# FPGA.net
KiCad netlist of a schematic drawn in Altium Designer
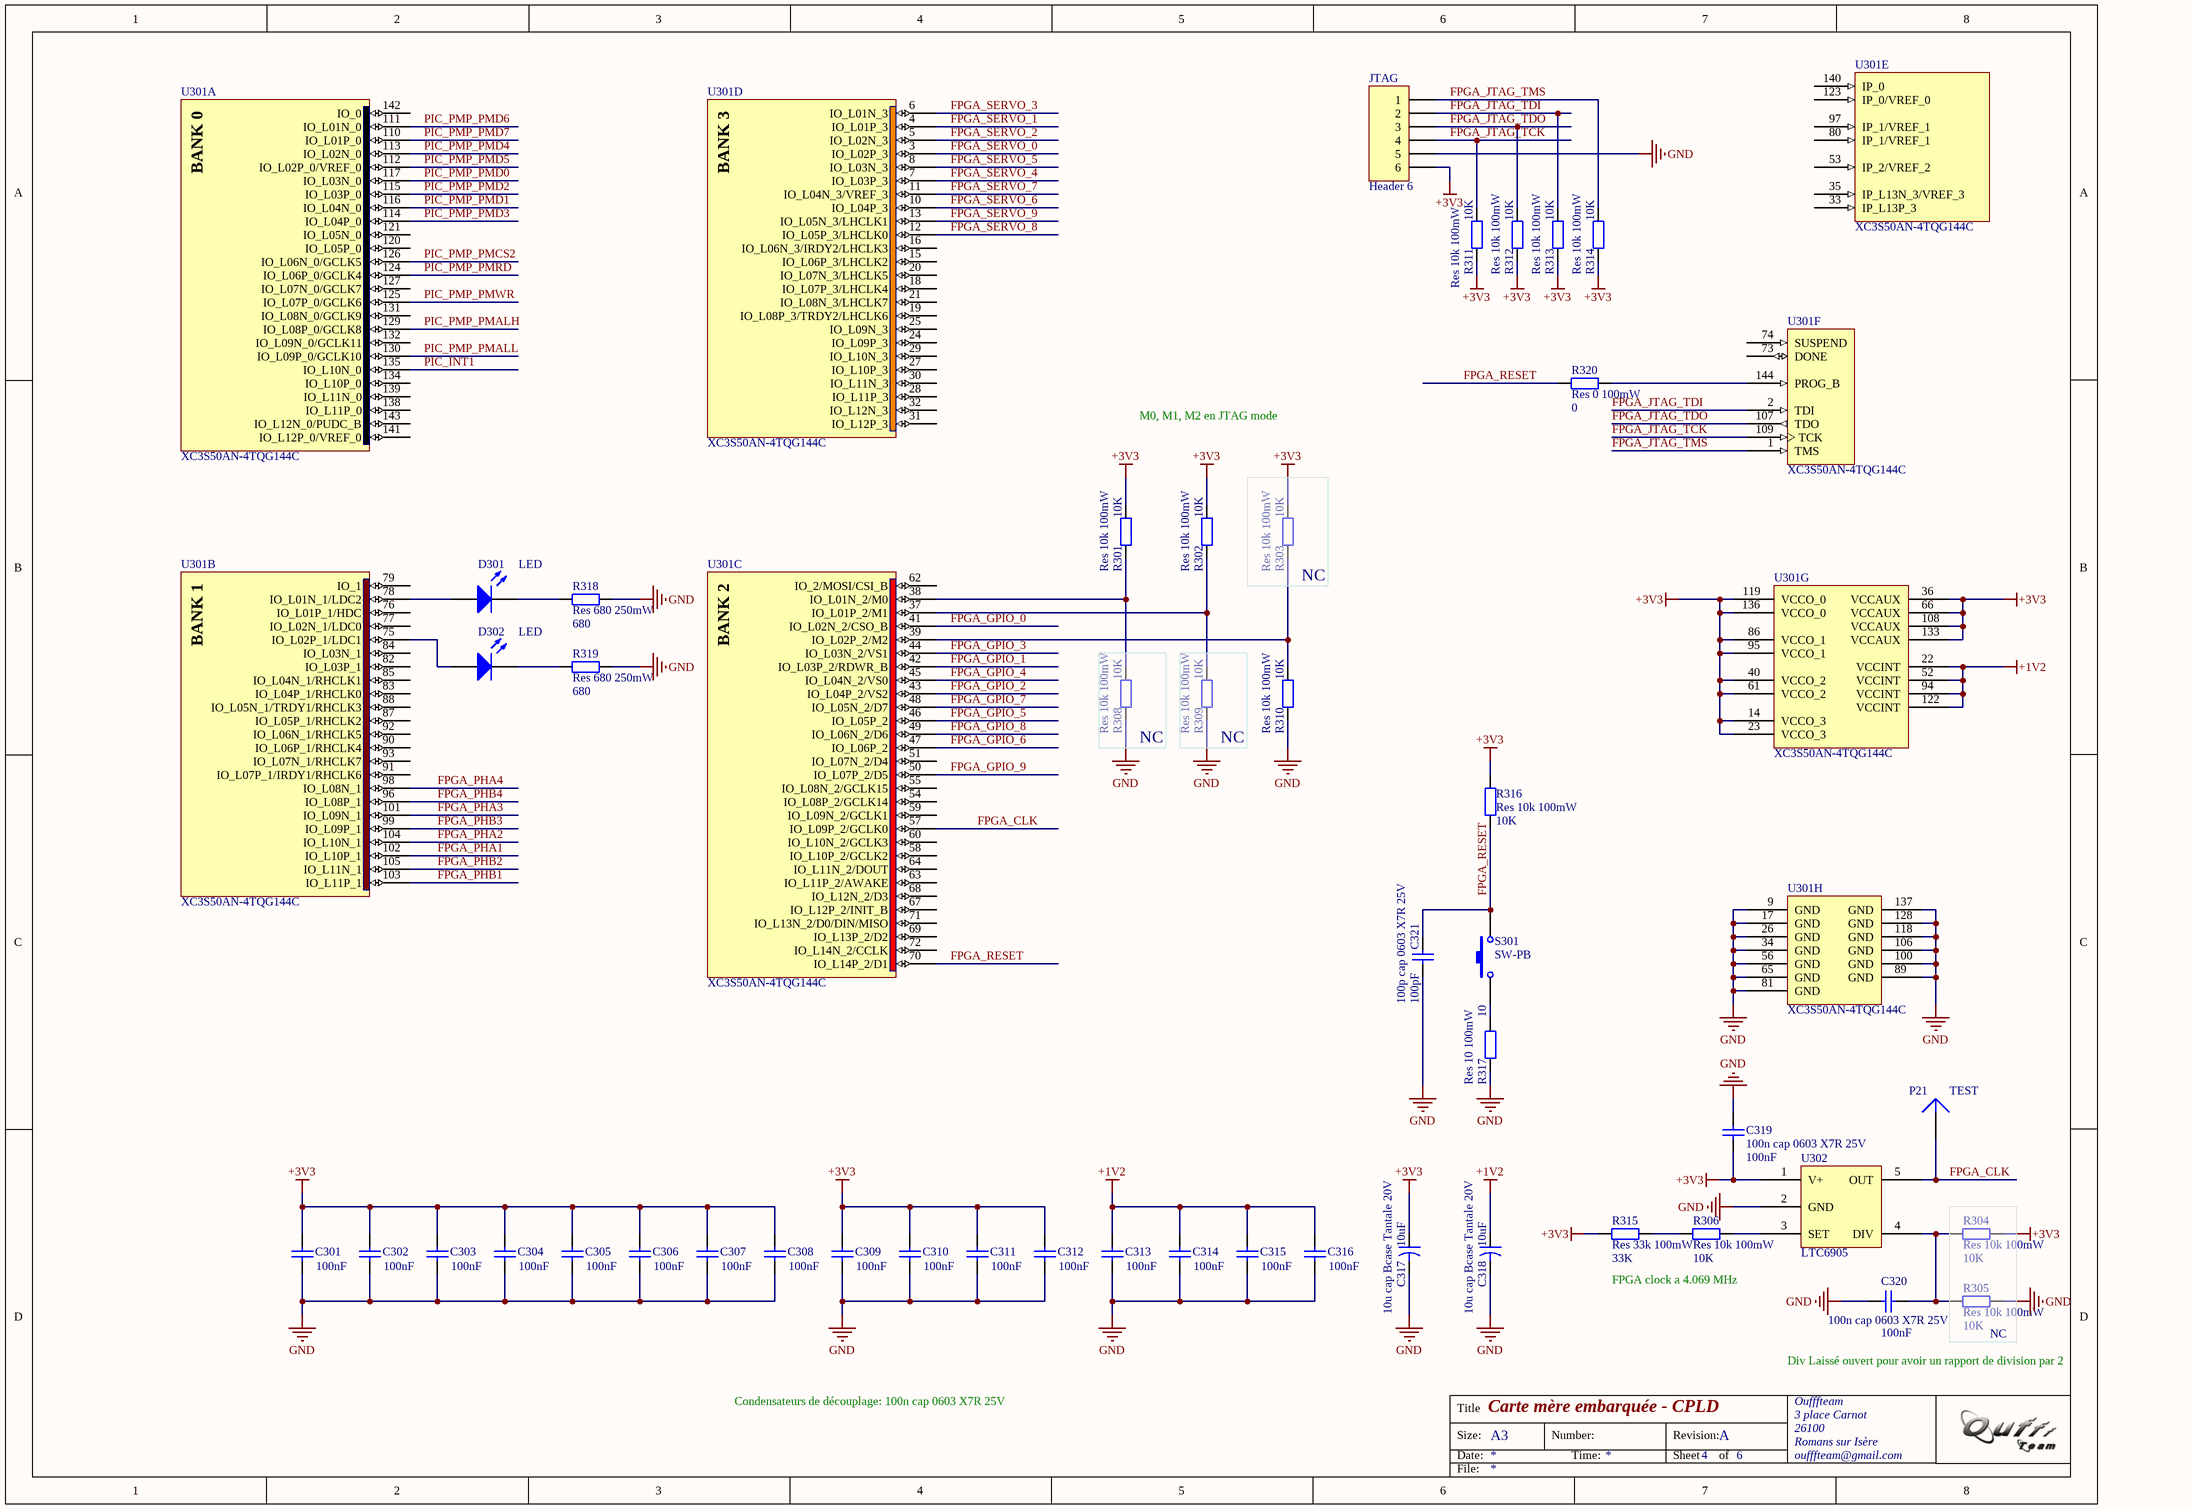
[diagram p0: FPGA.SchDoc]

(export (version "E")
  (design (tool "Eeschema 10.0.6"))
  (components
    (comp (ref "C301")
      (value "100nF")
      (footprint "1608[0603]")
      (description "Capacitor")
      (fields (field (name "Comment") "100n cap 0603 X7R 25V") (field (name "PUBLISHER") "Altium Limited"))
      (libsource (lib "Miscellaneous Devices") (part "Cap"))
    )
    (comp (ref "C302")
      (value "100nF")
      (footprint "1608[0603]")
      (description "Capacitor")
      (fields (field (name "Comment") "100n cap 0603 X7R 25V") (field (name "PUBLISHER") "Altium Limited"))
      (libsource (lib "Miscellaneous Devices") (part "Cap"))
    )
    (comp (ref "C303")
      (value "100nF")
      (footprint "1608[0603]")
      (description "Capacitor")
      (fields (field (name "Comment") "100n cap 0603 X7R 25V") (field (name "PUBLISHER") "Altium Limited"))
      (libsource (lib "Miscellaneous Devices") (part "Cap"))
    )
    (comp (ref "C304")
      (value "100nF")
      (footprint "1608[0603]")
      (description "Capacitor")
      (fields (field (name "Comment") "100n cap 0603 X7R 25V") (field (name "PUBLISHER") "Altium Limited"))
      (libsource (lib "Miscellaneous Devices") (part "Cap"))
    )
    (comp (ref "C305")
      (value "100nF")
      (footprint "1608[0603]")
      (description "Capacitor")
      (fields (field (name "Comment") "100n cap 0603 X7R 25V") (field (name "PUBLISHER") "Altium Limited"))
      (libsource (lib "Miscellaneous Devices") (part "Cap"))
    )
    (comp (ref "C306")
      (value "100nF")
      (footprint "1608[0603]")
      (description "Capacitor")
      (fields (field (name "Comment") "100n cap 0603 X7R 25V") (field (name "PUBLISHER") "Altium Limited"))
      (libsource (lib "Miscellaneous Devices") (part "Cap"))
    )
    (comp (ref "C307")
      (value "100nF")
      (footprint "1608[0603]")
      (description "Capacitor")
      (fields (field (name "Comment") "100n cap 0603 X7R 25V") (field (name "PUBLISHER") "Altium Limited"))
      (libsource (lib "Miscellaneous Devices") (part "Cap"))
    )
    (comp (ref "C308")
      (value "100nF")
      (footprint "1608[0603]")
      (description "Capacitor")
      (fields (field (name "Comment") "100n cap 0603 X7R 25V") (field (name "PUBLISHER") "Altium Limited"))
      (libsource (lib "Miscellaneous Devices") (part "Cap"))
    )
    (comp (ref "C309")
      (value "100nF")
      (footprint "1608[0603]")
      (description "Capacitor")
      (fields (field (name "Comment") "100n cap 0603 X7R 25V") (field (name "PUBLISHER") "Altium Limited"))
      (libsource (lib "Miscellaneous Devices") (part "Cap"))
    )
    (comp (ref "C310")
      (value "100nF")
      (footprint "1608[0603]")
      (description "Capacitor")
      (fields (field (name "Comment") "100n cap 0603 X7R 25V") (field (name "PUBLISHER") "Altium Limited"))
      (libsource (lib "Miscellaneous Devices") (part "Cap"))
    )
    (comp (ref "C311")
      (value "100nF")
      (footprint "1608[0603]")
      (description "Capacitor")
      (fields (field (name "Comment") "100n cap 0603 X7R 25V") (field (name "PUBLISHER") "Altium Limited"))
      (libsource (lib "Miscellaneous Devices") (part "Cap"))
    )
    (comp (ref "C312")
      (value "100nF")
      (footprint "1608[0603]")
      (description "Capacitor")
      (fields (field (name "Comment") "100n cap 0603 X7R 25V") (field (name "PUBLISHER") "Altium Limited"))
      (libsource (lib "Miscellaneous Devices") (part "Cap"))
    )
    (comp (ref "C313")
      (value "100nF")
      (footprint "1608[0603]")
      (description "Capacitor")
      (fields (field (name "Comment") "100n cap 0603 X7R 25V") (field (name "PUBLISHER") "Altium Limited"))
      (libsource (lib "Miscellaneous Devices") (part "Cap"))
    )
    (comp (ref "C314")
      (value "100nF")
      (footprint "1608[0603]")
      (description "Capacitor")
      (fields (field (name "Comment") "100n cap 0603 X7R 25V") (field (name "PUBLISHER") "Altium Limited"))
      (libsource (lib "Miscellaneous Devices") (part "Cap"))
    )
    (comp (ref "C315")
      (value "100nF")
      (footprint "1608[0603]")
      (description "Capacitor")
      (fields (field (name "Comment") "100n cap 0603 X7R 25V") (field (name "PUBLISHER") "Altium Limited"))
      (libsource (lib "Miscellaneous Devices") (part "Cap"))
    )
    (comp (ref "C316")
      (value "100nF")
      (footprint "1608[0603]")
      (description "Capacitor")
      (fields (field (name "Comment") "100n cap 0603 X7R 25V") (field (name "PUBLISHER") "Altium Limited"))
      (libsource (lib "Miscellaneous Devices") (part "Cap"))
    )
    (comp (ref "C317")
      (value "10u cap Bcase Tantale 20V")
      (footprint "6032")
      (description "Capacitor")
      (fields (field (name "ALTIUM_VALUE") "10uF") (field (name "PUBLISHER") "Altium Limited"))
      (libsource (lib "Miscellaneous Devices") (part "Cap2"))
    )
    (comp (ref "C318")
      (value "10u cap Bcase Tantale 20V")
      (footprint "6032")
      (description "Capacitor")
      (fields (field (name "ALTIUM_VALUE") "10uF") (field (name "PUBLISHER") "Altium Limited"))
      (libsource (lib "Miscellaneous Devices") (part "Cap2"))
    )
    (comp (ref "C319")
      (value "100n cap 0603 X7R 25V")
      (footprint "1608[0603]")
      (description "Capacitor")
      (fields (field (name "ALTIUM_VALUE") "100nF") (field (name "PUBLISHER") "Altium Limited"))
      (libsource (lib "Miscellaneous Devices") (part "Cap"))
    )
    (comp (ref "C320")
      (value "100n cap 0603 X7R 25V")
      (footprint "1608[0603]")
      (description "Capacitor")
      (fields (field (name "ALTIUM_VALUE") "100nF") (field (name "PUBLISHER") "Altium Limited"))
      (libsource (lib "Miscellaneous Devices") (part "Cap"))
    )
    (comp (ref "C321")
      (value "100p cap 0603 X7R 25V")
      (footprint "1608[0603]")
      (description "Capacitor")
      (fields (field (name "ALTIUM_VALUE") "100pF") (field (name "PUBLISHER") "Altium Limited"))
      (libsource (lib "Miscellaneous Devices") (part "Cap"))
    )
    (comp (ref "D301")
      (value "LED")
      (footprint "1608[0603]")
      (description "LED SML-311DTT86")
      (fields (field (name "PUBLISHER") "Altium Limited"))
      (libsource (lib "Miscellaneous Devices") (part "LED0"))
    )
    (comp (ref "D302")
      (value "LED")
      (footprint "1608[0603]")
      (description "LED SML-311DTT86")
      (fields (field (name "PUBLISHER") "Altium Limited"))
      (libsource (lib "Miscellaneous Devices") (part "LED0"))
    )
    (comp (ref "JTAG")
      (value "Header 6")
      (footprint "HDR1X6")
      (description "Header, 6-Pin")
      (fields (field (name "PUBLISHER") "Altium Limited"))
      (libsource (lib "Miscellaneous Connectors") (part "Header 6"))
    )
    (comp (ref "P21")
      (value "TEST")
      (footprint "TP1")
      (description "Plug")
      (fields (field (name "PUBLISHER") "Altium Limited"))
      (libsource (lib "Miscellaneous Connectors") (part "Plug"))
    )
    (comp (ref "R301")
      (value "Res 10k 100mW")
      (footprint "1608[0603]")
      (description "Resistor")
      (fields (field (name "ALTIUM_VALUE") "10K") (field (name "PUBLISHER") "Altium Limited"))
      (libsource (lib "Miscellaneous Devices") (part "Res2"))
    )
    (comp (ref "R302")
      (value "Res 10k 100mW")
      (footprint "1608[0603]")
      (description "Resistor")
      (fields (field (name "ALTIUM_VALUE") "10K") (field (name "PUBLISHER") "Altium Limited"))
      (libsource (lib "Miscellaneous Devices") (part "Res2"))
    )
    (comp (ref "R303")
      (value "Res 10k 100mW")
      (footprint "1608[0603]")
      (description "Resistor")
      (fields (field (name "ALTIUM_VALUE") "10K") (field (name "PUBLISHER") "Altium Limited"))
      (libsource (lib "Miscellaneous Devices") (part "Res2"))
    )
    (comp (ref "R304")
      (value "Res 10k 100mW")
      (footprint "1608[0603]")
      (description "Resistor")
      (fields (field (name "ALTIUM_VALUE") "10K") (field (name "PUBLISHER") "Altium Limited"))
      (libsource (lib "") (part "Res2_1"))
    )
    (comp (ref "R305")
      (value "Res 10k 100mW")
      (footprint "1608[0603]")
      (description "Resistor")
      (fields (field (name "ALTIUM_VALUE") "10K") (field (name "PUBLISHER") "Altium Limited"))
      (libsource (lib "") (part "Res2_1"))
    )
    (comp (ref "R306")
      (value "Res 10k 100mW")
      (footprint "1608[0603]")
      (description "Resistor")
      (fields (field (name "ALTIUM_VALUE") "10K") (field (name "PUBLISHER") "Altium Limited"))
      (libsource (lib "") (part "Res2_1"))
    )
    (comp (ref "R308")
      (value "Res 10k 100mW")
      (footprint "1608[0603]")
      (description "Resistor")
      (fields (field (name "ALTIUM_VALUE") "10K") (field (name "PUBLISHER") "Altium Limited"))
      (libsource (lib "Miscellaneous Devices") (part "Res2"))
    )
    (comp (ref "R309")
      (value "Res 10k 100mW")
      (footprint "1608[0603]")
      (description "Resistor")
      (fields (field (name "ALTIUM_VALUE") "10K") (field (name "PUBLISHER") "Altium Limited"))
      (libsource (lib "Miscellaneous Devices") (part "Res2"))
    )
    (comp (ref "R310")
      (value "Res 10k 100mW")
      (footprint "1608[0603]")
      (description "Resistor")
      (fields (field (name "ALTIUM_VALUE") "10K") (field (name "PUBLISHER") "Altium Limited"))
      (libsource (lib "Miscellaneous Devices") (part "Res2"))
    )
    (comp (ref "R311")
      (value "Res 10k 100mW")
      (footprint "1608[0603]")
      (description "Resistor")
      (fields (field (name "ALTIUM_VALUE") "10K") (field (name "PUBLISHER") "Altium Limited"))
      (libsource (lib "Miscellaneous Devices") (part "Res2"))
    )
    (comp (ref "R312")
      (value "Res 10k 100mW")
      (footprint "1608[0603]")
      (description "Resistor")
      (fields (field (name "ALTIUM_VALUE") "10K") (field (name "PUBLISHER") "Altium Limited"))
      (libsource (lib "Miscellaneous Devices") (part "Res2"))
    )
    (comp (ref "R313")
      (value "Res 10k 100mW")
      (footprint "1608[0603]")
      (description "Resistor")
      (fields (field (name "ALTIUM_VALUE") "10K") (field (name "PUBLISHER") "Altium Limited"))
      (libsource (lib "Miscellaneous Devices") (part "Res2"))
    )
    (comp (ref "R314")
      (value "Res 10k 100mW")
      (footprint "1608[0603]")
      (description "Resistor")
      (fields (field (name "ALTIUM_VALUE") "10K") (field (name "PUBLISHER") "Altium Limited"))
      (libsource (lib "Miscellaneous Devices") (part "Res2"))
    )
    (comp (ref "R315")
      (value "Res 33k 100mW")
      (footprint "1608[0603]")
      (description "Resistor")
      (fields (field (name "ALTIUM_VALUE") "33K") (field (name "PUBLISHER") "Altium Limited"))
      (libsource (lib "") (part "Res2_1"))
    )
    (comp (ref "R316")
      (value "Res 10k 100mW")
      (footprint "1608[0603]")
      (description "Resistor")
      (fields (field (name "ALTIUM_VALUE") "10K") (field (name "PUBLISHER") "Altium Limited"))
      (libsource (lib "Miscellaneous Devices") (part "Res2"))
    )
    (comp (ref "R317")
      (value "Res 10 100mW")
      (footprint "1608[0603]")
      (description "Resistor")
      (fields (field (name "ALTIUM_VALUE") "10") (field (name "PUBLISHER") "Altium Limited"))
      (libsource (lib "Miscellaneous Devices") (part "Res2"))
    )
    (comp (ref "R318")
      (value "Res 680 250mW")
      (footprint "1608[0603]")
      (description "Resistor")
      (fields (field (name "ALTIUM_VALUE") "680") (field (name "PUBLISHER") "Altium Limited"))
      (libsource (lib "") (part "Res2_1"))
    )
    (comp (ref "R319")
      (value "Res 680 250mW")
      (footprint "1608[0603]")
      (description "Resistor")
      (fields (field (name "ALTIUM_VALUE") "680") (field (name "PUBLISHER") "Altium Limited"))
      (libsource (lib "") (part "Res2_1"))
    )
    (comp (ref "R320")
      (value "Res 0 100mW")
      (footprint "1608[0603]")
      (description "Resistor")
      (fields (field (name "ALTIUM_VALUE") "0") (field (name "PUBLISHER") "Altium Limited"))
      (libsource (lib "") (part "Res2_1"))
    )
    (comp (ref "S301")
      (value "SW-PB")
      (footprint "BP1")
      (description "Switch")
      (fields (field (name "PUBLISHER") "Altium Limited"))
      (libsource (lib "Miscellaneous Devices") (part "SW-PB"))
    )
    (comp (ref "U301")
      (value "XC3S50AN-4TQG144C")
      (footprint "TQG144_N")
      (fields (field (name "PUBLISHER") "Altium Limited"))
      (libsource (lib "Xilinx Spartan-3AN") (part "XC3S50AN-4TQG144C"))
    )
    (comp (ref "U302")
      (value "LTC6905")
      (footprint "S5")
      (description "17MHz to 170MHz Resistor Set SOT-23 Oscillator")
      (libsource (lib "Oufff_Lib") (part "LTC6905"))
    )
  )
  (nets
    (net (code "1") (name "+1V2") (class "Default")
      (node (ref "C313") (pin "2") (pinfunction "2_2") (pintype "passive"))
      (node (ref "C314") (pin "2") (pinfunction "2_2") (pintype "passive"))
      (node (ref "C315") (pin "2") (pinfunction "2_2") (pintype "passive"))
      (node (ref "C316") (pin "2") (pinfunction "2_2") (pintype "passive"))
      (node (ref "C318") (pin "1") (pinfunction "1_1") (pintype "passive"))
      (node (ref "U301") (pin "122") (pinfunction "VCCINT_122") (pintype "power_in"))
      (node (ref "U301") (pin "22") (pinfunction "VCCINT_22") (pintype "power_in"))
      (node (ref "U301") (pin "52") (pinfunction "VCCINT_52") (pintype "power_in"))
      (node (ref "U301") (pin "94") (pinfunction "VCCINT_94") (pintype "power_in"))
    )
    (net (code "2") (name "+3V3") (class "Default")
      (node (ref "C301") (pin "2") (pinfunction "2_2") (pintype "passive"))
      (node (ref "C302") (pin "2") (pinfunction "2_2") (pintype "passive"))
      (node (ref "C303") (pin "2") (pinfunction "2_2") (pintype "passive"))
      (node (ref "C304") (pin "2") (pinfunction "2_2") (pintype "passive"))
      (node (ref "C305") (pin "2") (pinfunction "2_2") (pintype "passive"))
      (node (ref "C306") (pin "2") (pinfunction "2_2") (pintype "passive"))
      (node (ref "C307") (pin "2") (pinfunction "2_2") (pintype "passive"))
      (node (ref "C308") (pin "2") (pinfunction "2_2") (pintype "passive"))
      (node (ref "C309") (pin "2") (pinfunction "2_2") (pintype "passive"))
      (node (ref "C310") (pin "2") (pinfunction "2_2") (pintype "passive"))
      (node (ref "C311") (pin "2") (pinfunction "2_2") (pintype "passive"))
      (node (ref "C312") (pin "2") (pinfunction "2_2") (pintype "passive"))
      (node (ref "C317") (pin "1") (pinfunction "1_1") (pintype "passive"))
      (node (ref "C319") (pin "1") (pinfunction "1_1") (pintype "passive"))
      (node (ref "JTAG") (pin "6") (pinfunction "6_6") (pintype "passive"))
      (node (ref "R301") (pin "2") (pinfunction "2_2") (pintype "passive"))
      (node (ref "R302") (pin "2") (pinfunction "2_2") (pintype "passive"))
      (node (ref "R303") (pin "2") (pinfunction "2_2") (pintype "passive"))
      (node (ref "R304") (pin "2") (pinfunction "2_2") (pintype "passive"))
      (node (ref "R311") (pin "1") (pinfunction "1_1") (pintype "passive"))
      (node (ref "R312") (pin "1") (pinfunction "1_1") (pintype "passive"))
      (node (ref "R313") (pin "1") (pinfunction "1_1") (pintype "passive"))
      (node (ref "R314") (pin "1") (pinfunction "1_1") (pintype "passive"))
      (node (ref "R315") (pin "1") (pinfunction "1_1") (pintype "passive"))
      (node (ref "R316") (pin "2") (pinfunction "2_2") (pintype "passive"))
      (node (ref "U301") (pin "108") (pinfunction "VCCAUX_108") (pintype "power_in"))
      (node (ref "U301") (pin "119") (pinfunction "VCCO_0_119") (pintype "power_in"))
      (node (ref "U301") (pin "133") (pinfunction "VCCAUX_133") (pintype "power_in"))
      (node (ref "U301") (pin "136") (pinfunction "VCCO_0_136") (pintype "power_in"))
      (node (ref "U301") (pin "14") (pinfunction "VCCO_3_14") (pintype "power_in"))
      (node (ref "U301") (pin "23") (pinfunction "VCCO_3_23") (pintype "power_in"))
      (node (ref "U301") (pin "36") (pinfunction "VCCAUX_36") (pintype "power_in"))
      (node (ref "U301") (pin "40") (pinfunction "VCCO_2_40") (pintype "power_in"))
      (node (ref "U301") (pin "61") (pinfunction "VCCO_2_61") (pintype "power_in"))
      (node (ref "U301") (pin "66") (pinfunction "VCCAUX_66") (pintype "power_in"))
      (node (ref "U301") (pin "86") (pinfunction "VCCO_1_86") (pintype "power_in"))
      (node (ref "U301") (pin "95") (pinfunction "VCCO_1_95") (pintype "power_in"))
      (node (ref "U302") (pin "1") (pinfunction "V+_1") (pintype "passive"))
    )
    (net (code "3") (name "/FPGA_CLK") (class "Default")
      (node (ref "P21") (pin "1") (pinfunction "1_1") (pintype "passive"))
      (node (ref "U301") (pin "57") (pinfunction "IO_L09P_2/GCLK0_57") (pintype "bidirectional"))
      (node (ref "U302") (pin "5") (pinfunction "OUT_5") (pintype "passive"))
    )
    (net (code "4") (name "/FPGA_GPIO_0") (class "Default")
      (node (ref "U301") (pin "41") (pinfunction "IO_L02N_2/CSO_B_41") (pintype "bidirectional"))
    )
    (net (code "5") (name "/FPGA_GPIO_1") (class "Default")
      (node (ref "U301") (pin "42") (pinfunction "IO_L03P_2/RDWR_B_42") (pintype "bidirectional"))
    )
    (net (code "6") (name "/FPGA_GPIO_2") (class "Default")
      (node (ref "U301") (pin "43") (pinfunction "IO_L04P_2/VS2_43") (pintype "bidirectional"))
    )
    (net (code "7") (name "/FPGA_GPIO_3") (class "Default")
      (node (ref "U301") (pin "44") (pinfunction "IO_L03N_2/VS1_44") (pintype "bidirectional"))
    )
    (net (code "8") (name "/FPGA_GPIO_4") (class "Default")
      (node (ref "U301") (pin "45") (pinfunction "IO_L04N_2/VS0_45") (pintype "bidirectional"))
    )
    (net (code "9") (name "/FPGA_GPIO_5") (class "Default")
      (node (ref "U301") (pin "46") (pinfunction "IO_L05P_2_46") (pintype "bidirectional"))
    )
    (net (code "10") (name "/FPGA_GPIO_6") (class "Default")
      (node (ref "U301") (pin "47") (pinfunction "IO_L06P_2_47") (pintype "bidirectional"))
    )
    (net (code "11") (name "/FPGA_GPIO_7") (class "Default")
      (node (ref "U301") (pin "48") (pinfunction "IO_L05N_2/D7_48") (pintype "bidirectional"))
    )
    (net (code "12") (name "/FPGA_GPIO_8") (class "Default")
      (node (ref "U301") (pin "49") (pinfunction "IO_L06N_2/D6_49") (pintype "bidirectional"))
    )
    (net (code "13") (name "/FPGA_GPIO_9") (class "Default")
      (node (ref "U301") (pin "50") (pinfunction "IO_L07P_2/D5_50") (pintype "bidirectional"))
    )
    (net (code "14") (name "/FPGA_JTAG_TCK") (class "Default")
      (node (ref "JTAG") (pin "4") (pinfunction "4_4") (pintype "passive"))
      (node (ref "R311") (pin "2") (pinfunction "2_2") (pintype "passive"))
      (node (ref "U301") (pin "109") (pinfunction "TCK_109") (pintype "input"))
    )
    (net (code "15") (name "/FPGA_JTAG_TDI") (class "Default")
      (node (ref "JTAG") (pin "2") (pinfunction "2_2") (pintype "passive"))
      (node (ref "R313") (pin "2") (pinfunction "2_2") (pintype "passive"))
      (node (ref "U301") (pin "2") (pinfunction "TDI_2") (pintype "input"))
    )
    (net (code "16") (name "/FPGA_JTAG_TDO") (class "Default")
      (node (ref "JTAG") (pin "3") (pinfunction "3_3") (pintype "passive"))
      (node (ref "R312") (pin "2") (pinfunction "2_2") (pintype "passive"))
      (node (ref "U301") (pin "107") (pinfunction "TDO_107") (pintype "output"))
    )
    (net (code "17") (name "/FPGA_JTAG_TMS") (class "Default")
      (node (ref "JTAG") (pin "1") (pinfunction "1_1") (pintype "passive"))
      (node (ref "R314") (pin "2") (pinfunction "2_2") (pintype "passive"))
      (node (ref "U301") (pin "1") (pinfunction "TMS_1") (pintype "input"))
    )
    (net (code "18") (name "/FPGA_PHA1") (class "Default")
      (node (ref "U301") (pin "102") (pinfunction "IO_L10P_1_102") (pintype "bidirectional"))
    )
    (net (code "19") (name "/FPGA_PHA2") (class "Default")
      (node (ref "U301") (pin "104") (pinfunction "IO_L10N_1_104") (pintype "bidirectional"))
    )
    (net (code "20") (name "/FPGA_PHA3") (class "Default")
      (node (ref "U301") (pin "101") (pinfunction "IO_L09N_1_101") (pintype "bidirectional"))
    )
    (net (code "21") (name "/FPGA_PHA4") (class "Default")
      (node (ref "U301") (pin "98") (pinfunction "IO_L08N_1_98") (pintype "bidirectional"))
    )
    (net (code "22") (name "/FPGA_PHB1") (class "Default")
      (node (ref "U301") (pin "103") (pinfunction "IO_L11P_1_103") (pintype "bidirectional"))
    )
    (net (code "23") (name "/FPGA_PHB2") (class "Default")
      (node (ref "U301") (pin "105") (pinfunction "IO_L11N_1_105") (pintype "bidirectional"))
    )
    (net (code "24") (name "/FPGA_PHB3") (class "Default")
      (node (ref "U301") (pin "99") (pinfunction "IO_L09P_1_99") (pintype "bidirectional"))
    )
    (net (code "25") (name "/FPGA_PHB4") (class "Default")
      (node (ref "U301") (pin "96") (pinfunction "IO_L08P_1_96") (pintype "bidirectional"))
    )
    (net (code "26") (name "/FPGA_RESET") (class "Default")
      (node (ref "C321") (pin "2") (pinfunction "2_2") (pintype "passive"))
      (node (ref "R316") (pin "1") (pinfunction "1_1") (pintype "passive"))
      (node (ref "R320") (pin "1") (pinfunction "1_1") (pintype "passive"))
      (node (ref "S301") (pin "3") (pinfunction "3_3") (pintype "passive"))
      (node (ref "U301") (pin "70") (pinfunction "IO_L14P_2/D1_70") (pintype "bidirectional"))
    )
    (net (code "27") (name "/FPGA_SERVO_0") (class "Default")
      (node (ref "U301") (pin "3") (pinfunction "IO_L02P_3_3") (pintype "bidirectional"))
    )
    (net (code "28") (name "/FPGA_SERVO_1") (class "Default")
      (node (ref "U301") (pin "4") (pinfunction "IO_L01P_3_4") (pintype "bidirectional"))
    )
    (net (code "29") (name "/FPGA_SERVO_2") (class "Default")
      (node (ref "U301") (pin "5") (pinfunction "IO_L02N_3_5") (pintype "bidirectional"))
    )
    (net (code "30") (name "/FPGA_SERVO_3") (class "Default")
      (node (ref "U301") (pin "6") (pinfunction "IO_L01N_3_6") (pintype "bidirectional"))
    )
    (net (code "31") (name "/FPGA_SERVO_4") (class "Default")
      (node (ref "U301") (pin "7") (pinfunction "IO_L03P_3_7") (pintype "bidirectional"))
    )
    (net (code "32") (name "/FPGA_SERVO_5") (class "Default")
      (node (ref "U301") (pin "8") (pinfunction "IO_L03N_3_8") (pintype "bidirectional"))
    )
    (net (code "33") (name "/FPGA_SERVO_6") (class "Default")
      (node (ref "U301") (pin "10") (pinfunction "IO_L04P_3_10") (pintype "bidirectional"))
    )
    (net (code "34") (name "/FPGA_SERVO_7") (class "Default")
      (node (ref "U301") (pin "11") (pinfunction "IO_L04N_3/VREF_3_11") (pintype "bidirectional"))
    )
    (net (code "35") (name "/FPGA_SERVO_8") (class "Default")
      (node (ref "U301") (pin "12") (pinfunction "IO_L05P_3/LHCLK0_12") (pintype "bidirectional"))
    )
    (net (code "36") (name "/FPGA_SERVO_9") (class "Default")
      (node (ref "U301") (pin "13") (pinfunction "IO_L05N_3/LHCLK1_13") (pintype "bidirectional"))
    )
    (net (code "37") (name "/PIC_INT1") (class "Default")
      (node (ref "U301") (pin "135") (pinfunction "IO_L10N_0_135") (pintype "bidirectional"))
    )
    (net (code "38") (name "/PIC_PMP_PMALH") (class "Default")
      (node (ref "U301") (pin "129") (pinfunction "IO_L08P_0/GCLK8_129") (pintype "bidirectional"))
    )
    (net (code "39") (name "/PIC_PMP_PMALL") (class "Default")
      (node (ref "U301") (pin "130") (pinfunction "IO_L09P_0/GCLK10_130") (pintype "bidirectional"))
    )
    (net (code "40") (name "/PIC_PMP_PMCS2") (class "Default")
      (node (ref "U301") (pin "126") (pinfunction "IO_L06N_0/GCLK5_126") (pintype "bidirectional"))
    )
    (net (code "41") (name "/PIC_PMP_PMD0") (class "Default")
      (node (ref "U301") (pin "117") (pinfunction "IO_L03N_0_117") (pintype "bidirectional"))
    )
    (net (code "42") (name "/PIC_PMP_PMD1") (class "Default")
      (node (ref "U301") (pin "116") (pinfunction "IO_L04N_0_116") (pintype "bidirectional"))
    )
    (net (code "43") (name "/PIC_PMP_PMD2") (class "Default")
      (node (ref "U301") (pin "115") (pinfunction "IO_L03P_0_115") (pintype "bidirectional"))
    )
    (net (code "44") (name "/PIC_PMP_PMD3") (class "Default")
      (node (ref "U301") (pin "114") (pinfunction "IO_L04P_0_114") (pintype "bidirectional"))
    )
    (net (code "45") (name "/PIC_PMP_PMD4") (class "Default")
      (node (ref "U301") (pin "113") (pinfunction "IO_L02N_0_113") (pintype "bidirectional"))
    )
    (net (code "46") (name "/PIC_PMP_PMD5") (class "Default")
      (node (ref "U301") (pin "112") (pinfunction "IO_L02P_0/VREF_0_112") (pintype "bidirectional"))
    )
    (net (code "47") (name "/PIC_PMP_PMD6") (class "Default")
      (node (ref "U301") (pin "111") (pinfunction "IO_L01N_0_111") (pintype "bidirectional"))
    )
    (net (code "48") (name "/PIC_PMP_PMD7") (class "Default")
      (node (ref "U301") (pin "110") (pinfunction "IO_L01P_0_110") (pintype "bidirectional"))
    )
    (net (code "49") (name "/PIC_PMP_PMRD") (class "Default")
      (node (ref "U301") (pin "124") (pinfunction "IO_L06P_0/GCLK4_124") (pintype "bidirectional"))
    )
    (net (code "50") (name "/PIC_PMP_PMWR") (class "Default")
      (node (ref "U301") (pin "125") (pinfunction "IO_L07P_0/GCLK6_125") (pintype "bidirectional"))
    )
    (net (code "51") (name "GND") (class "Default")
      (node (ref "C301") (pin "1") (pinfunction "1_1") (pintype "passive"))
      (node (ref "C302") (pin "1") (pinfunction "1_1") (pintype "passive"))
      (node (ref "C303") (pin "1") (pinfunction "1_1") (pintype "passive"))
      (node (ref "C304") (pin "1") (pinfunction "1_1") (pintype "passive"))
      (node (ref "C305") (pin "1") (pinfunction "1_1") (pintype "passive"))
      (node (ref "C306") (pin "1") (pinfunction "1_1") (pintype "passive"))
      (node (ref "C307") (pin "1") (pinfunction "1_1") (pintype "passive"))
      (node (ref "C308") (pin "1") (pinfunction "1_1") (pintype "passive"))
      (node (ref "C309") (pin "1") (pinfunction "1_1") (pintype "passive"))
      (node (ref "C310") (pin "1") (pinfunction "1_1") (pintype "passive"))
      (node (ref "C311") (pin "1") (pinfunction "1_1") (pintype "passive"))
      (node (ref "C312") (pin "1") (pinfunction "1_1") (pintype "passive"))
      (node (ref "C313") (pin "1") (pinfunction "1_1") (pintype "passive"))
      (node (ref "C314") (pin "1") (pinfunction "1_1") (pintype "passive"))
      (node (ref "C315") (pin "1") (pinfunction "1_1") (pintype "passive"))
      (node (ref "C316") (pin "1") (pinfunction "1_1") (pintype "passive"))
      (node (ref "C317") (pin "2") (pinfunction "2_2") (pintype "passive"))
      (node (ref "C318") (pin "2") (pinfunction "2_2") (pintype "passive"))
      (node (ref "C319") (pin "2") (pinfunction "2_2") (pintype "passive"))
      (node (ref "C320") (pin "1") (pinfunction "1_1") (pintype "passive"))
      (node (ref "C321") (pin "1") (pinfunction "1_1") (pintype "passive"))
      (node (ref "JTAG") (pin "5") (pinfunction "5_5") (pintype "passive"))
      (node (ref "R305") (pin "2") (pinfunction "2_2") (pintype "passive"))
      (node (ref "R308") (pin "1") (pinfunction "1_1") (pintype "passive"))
      (node (ref "R309") (pin "1") (pinfunction "1_1") (pintype "passive"))
      (node (ref "R310") (pin "1") (pinfunction "1_1") (pintype "passive"))
      (node (ref "R317") (pin "1") (pinfunction "1_1") (pintype "passive"))
      (node (ref "R318") (pin "2") (pinfunction "2_2") (pintype "passive"))
      (node (ref "R319") (pin "2") (pinfunction "2_2") (pintype "passive"))
      (node (ref "U301") (pin "100") (pinfunction "GND_100") (pintype "power_in"))
      (node (ref "U301") (pin "106") (pinfunction "GND_106") (pintype "power_in"))
      (node (ref "U301") (pin "118") (pinfunction "GND_118") (pintype "power_in"))
      (node (ref "U301") (pin "128") (pinfunction "GND_128") (pintype "power_in"))
      (node (ref "U301") (pin "137") (pinfunction "GND_137") (pintype "power_in"))
      (node (ref "U301") (pin "17") (pinfunction "GND_17") (pintype "power_in"))
      (node (ref "U301") (pin "26") (pinfunction "GND_26") (pintype "power_in"))
      (node (ref "U301") (pin "34") (pinfunction "GND_34") (pintype "power_in"))
      (node (ref "U301") (pin "56") (pinfunction "GND_56") (pintype "power_in"))
      (node (ref "U301") (pin "65") (pinfunction "GND_65") (pintype "power_in"))
      (node (ref "U301") (pin "81") (pinfunction "GND_81") (pintype "power_in"))
      (node (ref "U301") (pin "89") (pinfunction "GND_89") (pintype "power_in"))
      (node (ref "U301") (pin "9") (pinfunction "GND_9") (pintype "power_in"))
      (node (ref "U302") (pin "2") (pinfunction "GND_2") (pintype "passive"))
    )
    (net (code "52") (name "Net-(D301-A)") (class "Default")
      (node (ref "D301") (pin "1") (pinfunction "A_1") (pintype "passive"))
      (node (ref "U301") (pin "78") (pinfunction "IO_L01N_1/LDC2_78") (pintype "bidirectional"))
    )
    (net (code "53") (name "Net-(D301-K)") (class "Default")
      (node (ref "D301") (pin "2") (pinfunction "K_2") (pintype "passive"))
      (node (ref "R318") (pin "1") (pinfunction "1_1") (pintype "passive"))
    )
    (net (code "54") (name "Net-(D302-A)") (class "Default")
      (node (ref "D302") (pin "1") (pinfunction "A_1") (pintype "passive"))
      (node (ref "U301") (pin "75") (pinfunction "IO_L02P_1/LDC1_75") (pintype "bidirectional"))
    )
    (net (code "55") (name "Net-(D302-K)") (class "Default")
      (node (ref "D302") (pin "2") (pinfunction "K_2") (pintype "passive"))
      (node (ref "R319") (pin "1") (pinfunction "1_1") (pintype "passive"))
    )
    (net (code "56") (name "Net-(R306-Pad1)") (class "Default")
      (node (ref "R306") (pin "1") (pinfunction "1_1") (pintype "passive"))
      (node (ref "R315") (pin "2") (pinfunction "2_2") (pintype "passive"))
    )
    (net (code "57") (name "Net-(R317-Pad2)") (class "Default")
      (node (ref "R317") (pin "2") (pinfunction "2_2") (pintype "passive"))
      (node (ref "S301") (pin "1") (pinfunction "1_1") (pintype "passive"))
    )
    (net (code "58") (name "Net-(U301C-IO_L01N_2{slash}M0)") (class "Default")
      (node (ref "R301") (pin "1") (pinfunction "1_1") (pintype "passive"))
      (node (ref "R308") (pin "2") (pinfunction "2_2") (pintype "passive"))
      (node (ref "U301") (pin "38") (pinfunction "IO_L01N_2/M0_38") (pintype "bidirectional"))
    )
    (net (code "59") (name "Net-(U301C-IO_L01P_2{slash}M1)") (class "Default")
      (node (ref "R302") (pin "1") (pinfunction "1_1") (pintype "passive"))
      (node (ref "R309") (pin "2") (pinfunction "2_2") (pintype "passive"))
      (node (ref "U301") (pin "37") (pinfunction "IO_L01P_2/M1_37") (pintype "bidirectional"))
    )
    (net (code "60") (name "Net-(U301C-IO_L02P_2{slash}M2)") (class "Default")
      (node (ref "R303") (pin "1") (pinfunction "1_1") (pintype "passive"))
      (node (ref "R310") (pin "2") (pinfunction "2_2") (pintype "passive"))
      (node (ref "U301") (pin "39") (pinfunction "IO_L02P_2/M2_39") (pintype "bidirectional"))
    )
    (net (code "61") (name "Net-(U301F-PROG_B)") (class "Default")
      (node (ref "R320") (pin "2") (pinfunction "2_2") (pintype "passive"))
      (node (ref "U301") (pin "144") (pinfunction "PROG_B_144") (pintype "input"))
    )
    (net (code "62") (name "Net-(U302-DIV)") (class "Default")
      (node (ref "C320") (pin "2") (pinfunction "2_2") (pintype "passive"))
      (node (ref "R304") (pin "1") (pinfunction "1_1") (pintype "passive"))
      (node (ref "R305") (pin "1") (pinfunction "1_1") (pintype "passive"))
      (node (ref "U302") (pin "4") (pinfunction "DIV_4") (pintype "passive"))
    )
    (net (code "63") (name "Net-(U302-SET)") (class "Default")
      (node (ref "R306") (pin "2") (pinfunction "2_2") (pintype "passive"))
      (node (ref "U302") (pin "3") (pinfunction "SET_3") (pintype "passive"))
    )
    (net (code "64") (name "unconnected-(U301A-IO_0-Pad142)") (class "Default")
      (node (ref "U301") (pin "142") (pinfunction "IO_0_142") (pintype "bidirectional"))
    )
    (net (code "65") (name "unconnected-(U301A-IO_L05N_0-Pad121)") (class "Default")
      (node (ref "U301") (pin "121") (pinfunction "IO_L05N_0_121") (pintype "bidirectional"))
    )
    (net (code "66") (name "unconnected-(U301A-IO_L05P_0-Pad120)") (class "Default")
      (node (ref "U301") (pin "120") (pinfunction "IO_L05P_0_120") (pintype "bidirectional"))
    )
    (net (code "67") (name "unconnected-(U301A-IO_L07N_0{slash}GCLK7-Pad127)") (class "Default")
      (node (ref "U301") (pin "127") (pinfunction "IO_L07N_0/GCLK7_127") (pintype "bidirectional"))
    )
    (net (code "68") (name "unconnected-(U301A-IO_L08N_0{slash}GCLK9-Pad131)") (class "Default")
      (node (ref "U301") (pin "131") (pinfunction "IO_L08N_0/GCLK9_131") (pintype "bidirectional"))
    )
    (net (code "69") (name "unconnected-(U301A-IO_L09N_0{slash}GCLK11-Pad132)") (class "Default")
      (node (ref "U301") (pin "132") (pinfunction "IO_L09N_0/GCLK11_132") (pintype "bidirectional"))
    )
    (net (code "70") (name "unconnected-(U301A-IO_L10P_0-Pad134)") (class "Default")
      (node (ref "U301") (pin "134") (pinfunction "IO_L10P_0_134") (pintype "bidirectional"))
    )
    (net (code "71") (name "unconnected-(U301A-IO_L11N_0-Pad139)") (class "Default")
      (node (ref "U301") (pin "139") (pinfunction "IO_L11N_0_139") (pintype "bidirectional"))
    )
    (net (code "72") (name "unconnected-(U301A-IO_L11P_0-Pad138)") (class "Default")
      (node (ref "U301") (pin "138") (pinfunction "IO_L11P_0_138") (pintype "bidirectional"))
    )
    (net (code "73") (name "unconnected-(U301A-IO_L12N_0{slash}PUDC_B-Pad143)") (class "Default")
      (node (ref "U301") (pin "143") (pinfunction "IO_L12N_0/PUDC_B_143") (pintype "bidirectional"))
    )
    (net (code "74") (name "unconnected-(U301A-IO_L12P_0{slash}VREF_0-Pad141)") (class "Default")
      (node (ref "U301") (pin "141") (pinfunction "IO_L12P_0/VREF_0_141") (pintype "bidirectional"))
    )
    (net (code "75") (name "unconnected-(U301B-IO_1-Pad79)") (class "Default")
      (node (ref "U301") (pin "79") (pinfunction "IO_1_79") (pintype "bidirectional"))
    )
    (net (code "76") (name "unconnected-(U301B-IO_L01P_1{slash}HDC-Pad76)") (class "Default")
      (node (ref "U301") (pin "76") (pinfunction "IO_L01P_1/HDC_76") (pintype "bidirectional"))
    )
    (net (code "77") (name "unconnected-(U301B-IO_L02N_1{slash}LDC0-Pad77)") (class "Default")
      (node (ref "U301") (pin "77") (pinfunction "IO_L02N_1/LDC0_77") (pintype "bidirectional"))
    )
    (net (code "78") (name "unconnected-(U301B-IO_L03N_1-Pad84)") (class "Default")
      (node (ref "U301") (pin "84") (pinfunction "IO_L03N_1_84") (pintype "bidirectional"))
    )
    (net (code "79") (name "unconnected-(U301B-IO_L03P_1-Pad82)") (class "Default")
      (node (ref "U301") (pin "82") (pinfunction "IO_L03P_1_82") (pintype "bidirectional"))
    )
    (net (code "80") (name "unconnected-(U301B-IO_L04N_1{slash}RHCLK1-Pad85)") (class "Default")
      (node (ref "U301") (pin "85") (pinfunction "IO_L04N_1/RHCLK1_85") (pintype "bidirectional"))
    )
    (net (code "81") (name "unconnected-(U301B-IO_L04P_1{slash}RHCLK0-Pad83)") (class "Default")
      (node (ref "U301") (pin "83") (pinfunction "IO_L04P_1/RHCLK0_83") (pintype "bidirectional"))
    )
    (net (code "82") (name "unconnected-(U301B-IO_L05N_1{slash}TRDY1{slash}RHCLK3-Pad88)") (class "Default")
      (node (ref "U301") (pin "88") (pinfunction "IO_L05N_1/TRDY1/RHCLK3_88") (pintype "bidirectional"))
    )
    (net (code "83") (name "unconnected-(U301B-IO_L05P_1{slash}RHCLK2-Pad87)") (class "Default")
      (node (ref "U301") (pin "87") (pinfunction "IO_L05P_1/RHCLK2_87") (pintype "bidirectional"))
    )
    (net (code "84") (name "unconnected-(U301B-IO_L06N_1{slash}RHCLK5-Pad92)") (class "Default")
      (node (ref "U301") (pin "92") (pinfunction "IO_L06N_1/RHCLK5_92") (pintype "bidirectional"))
    )
    (net (code "85") (name "unconnected-(U301B-IO_L06P_1{slash}RHCLK4-Pad90)") (class "Default")
      (node (ref "U301") (pin "90") (pinfunction "IO_L06P_1/RHCLK4_90") (pintype "bidirectional"))
    )
    (net (code "86") (name "unconnected-(U301B-IO_L07N_1{slash}RHCLK7-Pad93)") (class "Default")
      (node (ref "U301") (pin "93") (pinfunction "IO_L07N_1/RHCLK7_93") (pintype "bidirectional"))
    )
    (net (code "87") (name "unconnected-(U301B-IO_L07P_1{slash}IRDY1{slash}RHCLK6-Pad91)") (class "Default")
      (node (ref "U301") (pin "91") (pinfunction "IO_L07P_1/IRDY1/RHCLK6_91") (pintype "bidirectional"))
    )
    (net (code "88") (name "unconnected-(U301C-IO_2{slash}MOSI{slash}CSI_B-Pad62)") (class "Default")
      (node (ref "U301") (pin "62") (pinfunction "IO_2/MOSI/CSI_B_62") (pintype "bidirectional"))
    )
    (net (code "89") (name "unconnected-(U301C-IO_L07N_2{slash}D4-Pad51)") (class "Default")
      (node (ref "U301") (pin "51") (pinfunction "IO_L07N_2/D4_51") (pintype "bidirectional"))
    )
    (net (code "90") (name "unconnected-(U301C-IO_L08N_2{slash}GCLK15-Pad55)") (class "Default")
      (node (ref "U301") (pin "55") (pinfunction "IO_L08N_2/GCLK15_55") (pintype "bidirectional"))
    )
    (net (code "91") (name "unconnected-(U301C-IO_L08P_2{slash}GCLK14-Pad54)") (class "Default")
      (node (ref "U301") (pin "54") (pinfunction "IO_L08P_2/GCLK14_54") (pintype "bidirectional"))
    )
    (net (code "92") (name "unconnected-(U301C-IO_L09N_2{slash}GCLK1-Pad59)") (class "Default")
      (node (ref "U301") (pin "59") (pinfunction "IO_L09N_2/GCLK1_59") (pintype "bidirectional"))
    )
    (net (code "93") (name "unconnected-(U301C-IO_L10N_2{slash}GCLK3-Pad60)") (class "Default")
      (node (ref "U301") (pin "60") (pinfunction "IO_L10N_2/GCLK3_60") (pintype "bidirectional"))
    )
    (net (code "94") (name "unconnected-(U301C-IO_L10P_2{slash}GCLK2-Pad58)") (class "Default")
      (node (ref "U301") (pin "58") (pinfunction "IO_L10P_2/GCLK2_58") (pintype "bidirectional"))
    )
    (net (code "95") (name "unconnected-(U301C-IO_L11N_2{slash}DOUT-Pad64)") (class "Default")
      (node (ref "U301") (pin "64") (pinfunction "IO_L11N_2/DOUT_64") (pintype "bidirectional"))
    )
    (net (code "96") (name "unconnected-(U301C-IO_L11P_2{slash}AWAKE-Pad63)") (class "Default")
      (node (ref "U301") (pin "63") (pinfunction "IO_L11P_2/AWAKE_63") (pintype "bidirectional"))
    )
    (net (code "97") (name "unconnected-(U301C-IO_L12N_2{slash}D3-Pad68)") (class "Default")
      (node (ref "U301") (pin "68") (pinfunction "IO_L12N_2/D3_68") (pintype "bidirectional"))
    )
    (net (code "98") (name "unconnected-(U301C-IO_L12P_2{slash}INIT_B-Pad67)") (class "Default")
      (node (ref "U301") (pin "67") (pinfunction "IO_L12P_2/INIT_B_67") (pintype "bidirectional"))
    )
    (net (code "99") (name "unconnected-(U301C-IO_L13N_2{slash}D0{slash}DIN{slash}MISO-Pad71)") (class "Default")
      (node (ref "U301") (pin "71") (pinfunction "IO_L13N_2/D0/DIN/MISO_71") (pintype "bidirectional"))
    )
    (net (code "100") (name "unconnected-(U301C-IO_L13P_2{slash}D2-Pad69)") (class "Default")
      (node (ref "U301") (pin "69") (pinfunction "IO_L13P_2/D2_69") (pintype "bidirectional"))
    )
    (net (code "101") (name "unconnected-(U301C-IO_L14N_2{slash}CCLK-Pad72)") (class "Default")
      (node (ref "U301") (pin "72") (pinfunction "IO_L14N_2/CCLK_72") (pintype "bidirectional"))
    )
    (net (code "102") (name "unconnected-(U301D-IO_L06N_3{slash}IRDY2{slash}LHCLK3-Pad16)") (class "Default")
      (node (ref "U301") (pin "16") (pinfunction "IO_L06N_3/IRDY2/LHCLK3_16") (pintype "bidirectional"))
    )
    (net (code "103") (name "unconnected-(U301D-IO_L06P_3{slash}LHCLK2-Pad15)") (class "Default")
      (node (ref "U301") (pin "15") (pinfunction "IO_L06P_3/LHCLK2_15") (pintype "bidirectional"))
    )
    (net (code "104") (name "unconnected-(U301D-IO_L07N_3{slash}LHCLK5-Pad20)") (class "Default")
      (node (ref "U301") (pin "20") (pinfunction "IO_L07N_3/LHCLK5_20") (pintype "bidirectional"))
    )
    (net (code "105") (name "unconnected-(U301D-IO_L07P_3{slash}LHCLK4-Pad18)") (class "Default")
      (node (ref "U301") (pin "18") (pinfunction "IO_L07P_3/LHCLK4_18") (pintype "bidirectional"))
    )
    (net (code "106") (name "unconnected-(U301D-IO_L08N_3{slash}LHCLK7-Pad21)") (class "Default")
      (node (ref "U301") (pin "21") (pinfunction "IO_L08N_3/LHCLK7_21") (pintype "bidirectional"))
    )
    (net (code "107") (name "unconnected-(U301D-IO_L08P_3{slash}TRDY2{slash}LHCLK6-Pad19)") (class "Default")
      (node (ref "U301") (pin "19") (pinfunction "IO_L08P_3/TRDY2/LHCLK6_19") (pintype "bidirectional"))
    )
    (net (code "108") (name "unconnected-(U301D-IO_L09N_3-Pad25)") (class "Default")
      (node (ref "U301") (pin "25") (pinfunction "IO_L09N_3_25") (pintype "bidirectional"))
    )
    (net (code "109") (name "unconnected-(U301D-IO_L09P_3-Pad24)") (class "Default")
      (node (ref "U301") (pin "24") (pinfunction "IO_L09P_3_24") (pintype "bidirectional"))
    )
    (net (code "110") (name "unconnected-(U301D-IO_L10N_3-Pad29)") (class "Default")
      (node (ref "U301") (pin "29") (pinfunction "IO_L10N_3_29") (pintype "bidirectional"))
    )
    (net (code "111") (name "unconnected-(U301D-IO_L10P_3-Pad27)") (class "Default")
      (node (ref "U301") (pin "27") (pinfunction "IO_L10P_3_27") (pintype "bidirectional"))
    )
    (net (code "112") (name "unconnected-(U301D-IO_L11N_3-Pad30)") (class "Default")
      (node (ref "U301") (pin "30") (pinfunction "IO_L11N_3_30") (pintype "bidirectional"))
    )
    (net (code "113") (name "unconnected-(U301D-IO_L11P_3-Pad28)") (class "Default")
      (node (ref "U301") (pin "28") (pinfunction "IO_L11P_3_28") (pintype "bidirectional"))
    )
    (net (code "114") (name "unconnected-(U301D-IO_L12N_3-Pad32)") (class "Default")
      (node (ref "U301") (pin "32") (pinfunction "IO_L12N_3_32") (pintype "bidirectional"))
    )
    (net (code "115") (name "unconnected-(U301D-IO_L12P_3-Pad31)") (class "Default")
      (node (ref "U301") (pin "31") (pinfunction "IO_L12P_3_31") (pintype "bidirectional"))
    )
    (net (code "116") (name "unconnected-(U301E-IP_0-Pad140)") (class "Default")
      (node (ref "U301") (pin "140") (pinfunction "IP_0_140") (pintype "input"))
    )
    (net (code "117") (name "unconnected-(U301E-IP_0{slash}VREF_0-Pad123)") (class "Default")
      (node (ref "U301") (pin "123") (pinfunction "IP_0/VREF_0_123") (pintype "input"))
    )
    (net (code "118") (name "unconnected-(U301E-IP_1{slash}VREF_1-Pad80)") (class "Default")
      (node (ref "U301") (pin "80") (pinfunction "IP_1/VREF_1_80") (pintype "input"))
    )
    (net (code "119") (name "unconnected-(U301E-IP_1{slash}VREF_1-Pad97)") (class "Default")
      (node (ref "U301") (pin "97") (pinfunction "IP_1/VREF_1_97") (pintype "input"))
    )
    (net (code "120") (name "unconnected-(U301E-IP_2{slash}VREF_2-Pad53)") (class "Default")
      (node (ref "U301") (pin "53") (pinfunction "IP_2/VREF_2_53") (pintype "input"))
    )
    (net (code "121") (name "unconnected-(U301E-IP_L13N_3{slash}VREF_3-Pad35)") (class "Default")
      (node (ref "U301") (pin "35") (pinfunction "IP_L13N_3/VREF_3_35") (pintype "input"))
    )
    (net (code "122") (name "unconnected-(U301E-IP_L13P_3-Pad33)") (class "Default")
      (node (ref "U301") (pin "33") (pinfunction "IP_L13P_3_33") (pintype "input"))
    )
    (net (code "123") (name "unconnected-(U301F-DONE-Pad73)") (class "Default")
      (node (ref "U301") (pin "73") (pinfunction "DONE_73") (pintype "bidirectional"))
    )
    (net (code "124") (name "unconnected-(U301F-SUSPEND-Pad74)") (class "Default")
      (node (ref "U301") (pin "74") (pinfunction "SUSPEND_74") (pintype "input"))
    )
  )
)
